# Schematics.net
KiCad netlist of a schematic drawn in EAGLE
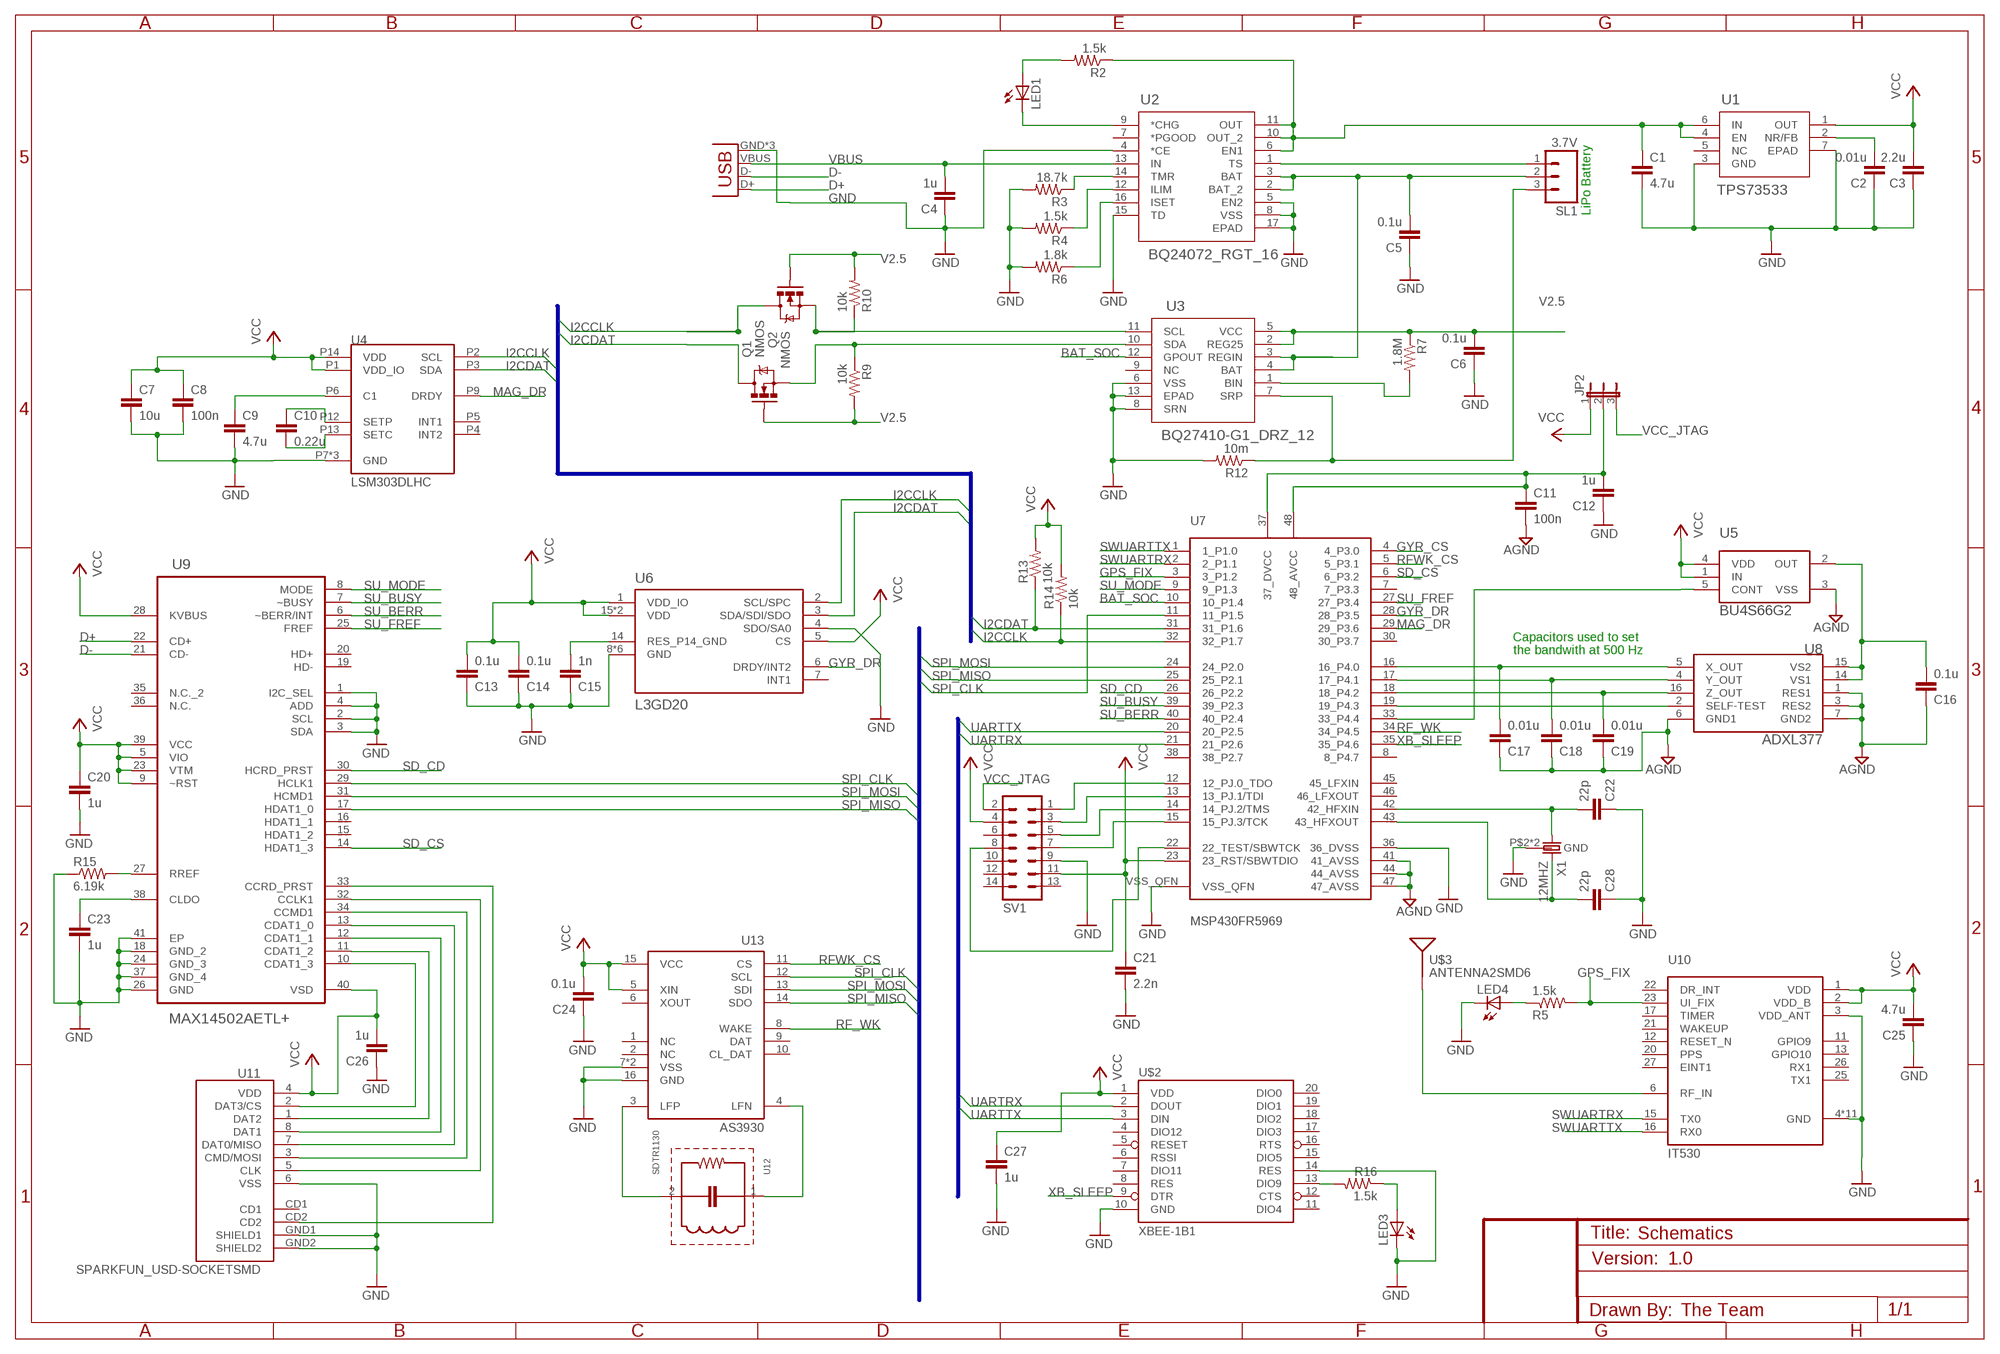
[diagram p0: schematic, sheet 1]

(export (version "E")
  (design (tool "Eeschema 10.0.6"))
  (components
    (comp (ref "C1")
      (value "4.7u")
      (footprint "eagle-import:C0603")
      (libsource (lib "eagle-import") (part "C-EUC0603"))
    )
    (comp (ref "C2")
      (value "0.01u")
      (footprint "eagle-import:C0603")
      (libsource (lib "eagle-import") (part "C-EUC0603"))
    )
    (comp (ref "C3")
      (value "2.2u")
      (footprint "eagle-import:C0603")
      (libsource (lib "eagle-import") (part "C-EUC0603"))
    )
    (comp (ref "C4")
      (value "1u")
      (footprint "eagle-import:C0603")
      (libsource (lib "eagle-import") (part "C-EUC0603"))
    )
    (comp (ref "C5")
      (value "0.1u")
      (footprint "eagle-import:C0603")
      (libsource (lib "eagle-import") (part "C-EUC0603"))
    )
    (comp (ref "C6")
      (value "0.1u")
      (footprint "eagle-import:C0603")
      (libsource (lib "eagle-import") (part "C-EUC0603"))
    )
    (comp (ref "C7")
      (value "10u")
      (footprint "eagle-import:C0603")
      (libsource (lib "eagle-import") (part "C-EUC0603"))
    )
    (comp (ref "C8")
      (value "100n")
      (footprint "eagle-import:C0603")
      (libsource (lib "eagle-import") (part "C-EUC0603"))
    )
    (comp (ref "C9")
      (value "4.7u")
      (footprint "eagle-import:C0603")
      (libsource (lib "eagle-import") (part "C-EUC0603"))
    )
    (comp (ref "C10")
      (value "0.22u")
      (footprint "eagle-import:C0603")
      (libsource (lib "eagle-import") (part "C-EUC0603"))
    )
    (comp (ref "C11")
      (value "100n")
      (footprint "eagle-import:C0603")
      (libsource (lib "eagle-import") (part "C-EUC0603"))
    )
    (comp (ref "C12")
      (value "1u")
      (footprint "eagle-import:C0603")
      (libsource (lib "eagle-import") (part "C-EUC0603"))
    )
    (comp (ref "C13")
      (value "0.1u")
      (footprint "eagle-import:C0603")
      (libsource (lib "eagle-import") (part "C-EUC0603"))
    )
    (comp (ref "C14")
      (value "0.1u")
      (footprint "eagle-import:C0603")
      (libsource (lib "eagle-import") (part "C-EUC0603"))
    )
    (comp (ref "C15")
      (value "1n")
      (footprint "eagle-import:C0603")
      (libsource (lib "eagle-import") (part "C-EUC0603"))
    )
    (comp (ref "C16")
      (value "0.1u")
      (footprint "eagle-import:C0603")
      (libsource (lib "eagle-import") (part "C-EUC0603"))
    )
    (comp (ref "C17")
      (value "0.01u")
      (footprint "eagle-import:C0603")
      (libsource (lib "eagle-import") (part "C-EUC0603"))
    )
    (comp (ref "C18")
      (value "0.01u")
      (footprint "eagle-import:C0603")
      (libsource (lib "eagle-import") (part "C-EUC0603"))
    )
    (comp (ref "C19")
      (value "0.01u")
      (footprint "eagle-import:C0603")
      (libsource (lib "eagle-import") (part "C-EUC0603"))
    )
    (comp (ref "C20")
      (value "1u")
      (footprint "eagle-import:C0603")
      (libsource (lib "eagle-import") (part "C-EUC0603"))
    )
    (comp (ref "C21")
      (value "2.2n")
      (footprint "eagle-import:C0603")
      (libsource (lib "eagle-import") (part "C-EUC0603"))
    )
    (comp (ref "C22")
      (value "22p")
      (footprint "eagle-import:C0603")
      (libsource (lib "eagle-import") (part "C-EUC0603"))
    )
    (comp (ref "C23")
      (value "1u")
      (footprint "eagle-import:C0603")
      (libsource (lib "eagle-import") (part "C-EUC0603"))
    )
    (comp (ref "C24")
      (value "0.1u")
      (footprint "eagle-import:C0603")
      (libsource (lib "eagle-import") (part "C-EUC0603"))
    )
    (comp (ref "C25")
      (value "4.7u")
      (footprint "eagle-import:C0603")
      (libsource (lib "eagle-import") (part "C-EUC0603"))
    )
    (comp (ref "C26")
      (value "1u")
      (footprint "eagle-import:C0603")
      (libsource (lib "eagle-import") (part "C-EUC0603"))
    )
    (comp (ref "C27")
      (value "1u")
      (footprint "eagle-import:C0603")
      (libsource (lib "eagle-import") (part "C-EUC0603"))
    )
    (comp (ref "C28")
      (value "22p")
      (footprint "eagle-import:C0603")
      (libsource (lib "eagle-import") (part "C-EUC0603"))
    )
    (comp (ref "JP1")
      (value "USB-MICROB")
      (footprint "eagle-import:USB-MICROB")
      (libsource (lib "eagle-import") (part "USB-MICROB"))
    )
    (comp (ref "JP2")
      (value "JP2E")
      (footprint "eagle-import:JP2")
      (libsource (lib "eagle-import") (part "JP2E"))
    )
    (comp (ref "LED1")
      (value "LED")
      (footprint "eagle-import:SMARTLED-TTW")
      (libsource (lib "eagle-import") (part "LED"))
    )
    (comp (ref "LED3")
      (value "LED")
      (footprint "eagle-import:SMARTLED-TTW")
      (libsource (lib "eagle-import") (part "LED"))
    )
    (comp (ref "LED4")
      (value "LED")
      (footprint "eagle-import:SMARTLED-TTW")
      (libsource (lib "eagle-import") (part "LED"))
    )
    (comp (ref "Q1")
      (value "NMOS")
      (footprint "eagle-import:SOT23")
      (libsource (lib "eagle-import") (part "MOSFET-NCHANNELBSS138"))
    )
    (comp (ref "Q2")
      (value "NMOS")
      (footprint "eagle-import:SOT23")
      (libsource (lib "eagle-import") (part "MOSFET-NCHANNELBSS138"))
    )
    (comp (ref "R2")
      (value "1.5k")
      (footprint "eagle-import:R0603")
      (libsource (lib "eagle-import") (part "R-US_R0603"))
    )
    (comp (ref "R3")
      (value "18.7k")
      (footprint "eagle-import:R0603")
      (libsource (lib "eagle-import") (part "R-US_R0603"))
    )
    (comp (ref "R4")
      (value "1.5k")
      (footprint "eagle-import:R0603")
      (libsource (lib "eagle-import") (part "R-US_R0603"))
    )
    (comp (ref "R5")
      (value "1.5k")
      (footprint "eagle-import:R0603")
      (libsource (lib "eagle-import") (part "R-US_R0603"))
    )
    (comp (ref "R6")
      (value "1.8k")
      (footprint "eagle-import:R0603")
      (libsource (lib "eagle-import") (part "R-US_R0603"))
    )
    (comp (ref "R7")
      (value "1.8M")
      (footprint "eagle-import:R0603")
      (libsource (lib "eagle-import") (part "R-US_R0603"))
    )
    (comp (ref "R9")
      (value "10k")
      (footprint "eagle-import:R0603")
      (libsource (lib "eagle-import") (part "R-US_R0603"))
    )
    (comp (ref "R10")
      (value "10k")
      (footprint "eagle-import:R0603")
      (libsource (lib "eagle-import") (part "R-US_R0603"))
    )
    (comp (ref "R12")
      (value "10m")
      (footprint "eagle-import:R0603")
      (libsource (lib "eagle-import") (part "R-US_R0603"))
    )
    (comp (ref "R13")
      (value "10k")
      (footprint "eagle-import:R0603")
      (libsource (lib "eagle-import") (part "R-US_R0603"))
    )
    (comp (ref "R14")
      (value "10k")
      (footprint "eagle-import:R0603")
      (libsource (lib "eagle-import") (part "R-US_R0603"))
    )
    (comp (ref "R15")
      (value "6.19k")
      (footprint "eagle-import:R0603")
      (libsource (lib "eagle-import") (part "R-US_R0603"))
    )
    (comp (ref "R16")
      (value "1.5k")
      (footprint "eagle-import:R0603")
      (libsource (lib "eagle-import") (part "R-US_R0603"))
    )
    (comp (ref "SL1")
      (value "3.7V")
      (footprint "eagle-import:03P")
      (libsource (lib "eagle-import") (part "M03"))
    )
    (comp (ref "SV1")
      (value "ML14L")
      (footprint "eagle-import:ML14L")
      (libsource (lib "eagle-import") (part "ML14L"))
    )
    (comp (ref "U$2")
      (value "XBEE-1B1")
      (footprint "eagle-import:XBEE-1")
      (libsource (lib "eagle-import") (part "XBEE-1B1"))
    )
    (comp (ref "U$3")
      (value "ANTENNA2SMD6")
      (footprint "eagle-import:ANTENNA-CHIP6")
      (libsource (lib "eagle-import") (part "ANTENNA2SMD6"))
    )
    (comp (ref "U1")
      (value "TPS73533")
      (footprint "eagle-import:DRV6_1P6X1")
      (fields
        (field (name "MANUFACTURER") "Texas Instruments")
        (field (name "MANUFACTURER_PART_NUMBER") "tps73533_drv_6")
      )
      (libsource (lib "eagle-import") (part "TPS73533_DRV_6"))
    )
    (comp (ref "U2")
      (value "BQ24072_RGT_16")
      (footprint "eagle-import:RGT16_1P7X1P7")
      (fields
        (field (name "GENERIC_PART_NUMBER") "BQ24072")
        (field (name "MANUFACTURER") "Texas Instruments")
      )
      (libsource (lib "eagle-import") (part "BQ24072_RGT_16"))
    )
    (comp (ref "U3")
      (value "BQ27410-G1_DRZ_12")
      (footprint "eagle-import:DRZ12_1P95X2P45")
      (fields
        (field (name "GENERIC_PART_NUMBER") "BQ27410-G1")
        (field (name "MANUFACTURER") "Texas Instruments")
      )
      (libsource (lib "eagle-import") (part "BQ27410-G1_DRZ_12"))
    )
    (comp (ref "U4")
      (value "LSM303DLHC")
      (footprint "eagle-import:LGA_3X5X1_14L")
      (libsource (lib "eagle-import") (part "LSM303DLHC"))
    )
    (comp (ref "U5")
      (value "BU4S66G2")
      (footprint "eagle-import:SSOP5")
      (libsource (lib "eagle-import") (part "BU4S66G2"))
    )
    (comp (ref "U6")
      (value "L3GD20")
      (footprint "eagle-import:L3GD20")
      (libsource (lib "eagle-import") (part "L3GD20"))
    )
    (comp (ref "U7")
      (value "MSP430FR5969")
      (footprint "eagle-import:RGZ(S-PQFP-N48)")
      (libsource (lib "eagle-import") (part "MSP430FR5969"))
    )
    (comp (ref "U8")
      (value "ADXL377")
      (footprint "eagle-import:LFCSP-16")
      (libsource (lib "eagle-import") (part "ADXL377"))
    )
    (comp (ref "U9")
      (value "MAX14502AETL+")
      (footprint "eagle-import:QFN40P500X500X80-41N")
      (libsource (lib "eagle-import") (part "MAX14502AETL+"))
    )
    (comp (ref "U10")
      (value "IT530")
      (footprint "eagle-import:IT530")
      (libsource (lib "eagle-import") (part "IT530"))
    )
    (comp (ref "U11")
      (value "SPARKFUN_USD-SOCKETSMD")
      (footprint "eagle-import:SPARKFUN_MICRO-SD-SOCKET-PP")
      (libsource (lib "eagle-import") (part "SPARKFUN_USD-SOCKETSMD"))
    )
    (comp (ref "U12")
      (value "SDTR1130")
      (footprint "eagle-import:SDTR1130-SMD")
      (libsource (lib "eagle-import") (part "SDTR1130"))
    )
    (comp (ref "U13")
      (value "AS3930")
      (footprint "eagle-import:AS3930")
      (libsource (lib "eagle-import") (part "AS3930"))
    )
    (comp (ref "X1")
      (value "12MHZ")
      (footprint "eagle-import:12MHZ")
      (libsource (lib "eagle-import") (part "12MHZ"))
    )
  )
  (nets
    (net (code "1") (name "/BAT_SOC") (class "Default")
      (node (ref "U3") (pin "12") (pinfunction "GPOUT_12") (pintype "output"))
      (node (ref "U7") (pin "10") (pinfunction "10_P1.4_10") (pintype "bidirectional"))
    )
    (net (code "2") (name "/D+") (class "Default")
      (node (ref "JP1") (pin "D+") (pinfunction "D+_D+") (pintype "bidirectional"))
      (node (ref "U9") (pin "22") (pinfunction "CD+_22") (pintype "passive"))
    )
    (net (code "3") (name "/D-") (class "Default")
      (node (ref "JP1") (pin "D-") (pinfunction "D-_D-") (pintype "bidirectional"))
      (node (ref "U9") (pin "21") (pinfunction "CD-_21") (pintype "passive"))
    )
    (net (code "4") (name "/GPS_FIX") (class "Default")
      (node (ref "R5") (pin "2") (pinfunction "2_2") (pintype "passive"))
      (node (ref "U10") (pin "23") (pinfunction "UI_FIX_23") (pintype "bidirectional"))
      (node (ref "U7") (pin "3") (pinfunction "3_P1.2_3") (pintype "bidirectional"))
    )
    (net (code "5") (name "/GYR_CS") (class "Default")
      (node (ref "U7") (pin "4") (pinfunction "4_P3.0_4") (pintype "bidirectional"))
    )
    (net (code "6") (name "/GYR_DR") (class "Default")
      (node (ref "U6") (pin "6") (pinfunction "DRDY/INT2_6") (pintype "output"))
      (node (ref "U7") (pin "28") (pinfunction "28_P3.5_28") (pintype "bidirectional"))
    )
    (net (code "7") (name "/I2CCLK") (class "Default")
      (node (ref "Q2") (pin "3") (pinfunction "D_3") (pintype "passive"))
      (node (ref "R14") (pin "1") (pinfunction "1_1") (pintype "passive"))
      (node (ref "U4") (pin "P2") (pinfunction "SCL_P2") (pintype "bidirectional"))
      (node (ref "U6") (pin "2") (pinfunction "SCL/SPC_2") (pintype "input"))
      (node (ref "U7") (pin "32") (pinfunction "32_P1.7_32") (pintype "bidirectional"))
    )
    (net (code "8") (name "/I2CDAT") (class "Default")
      (node (ref "Q1") (pin "3") (pinfunction "D_3") (pintype "passive"))
      (node (ref "R13") (pin "1") (pinfunction "1_1") (pintype "passive"))
      (node (ref "U4") (pin "P3") (pinfunction "SDA_P3") (pintype "bidirectional"))
      (node (ref "U6") (pin "3") (pinfunction "SDA/SDI/SDO_3") (pintype "bidirectional"))
      (node (ref "U7") (pin "31") (pinfunction "31_P1.6_31") (pintype "bidirectional"))
    )
    (net (code "9") (name "/MAG_DR") (class "Default")
      (node (ref "U4") (pin "P9") (pinfunction "DRDY_P9") (pintype "bidirectional"))
      (node (ref "U7") (pin "29") (pinfunction "29_P3.6_29") (pintype "bidirectional"))
    )
    (net (code "10") (name "/RFWK_CS") (class "Default")
      (node (ref "U13") (pin "11") (pinfunction "CS_11") (pintype "bidirectional"))
      (node (ref "U7") (pin "5") (pinfunction "5_P3.1_5") (pintype "bidirectional"))
    )
    (net (code "11") (name "/RF_WK") (class "Default")
      (node (ref "U13") (pin "8") (pinfunction "WAKE_8") (pintype "bidirectional"))
      (node (ref "U7") (pin "34") (pinfunction "34_P4.5_34") (pintype "bidirectional"))
    )
    (net (code "12") (name "/SD_CD") (class "Default")
      (node (ref "U7") (pin "26") (pinfunction "26_P2.2_26") (pintype "bidirectional"))
      (node (ref "U9") (pin "30") (pinfunction "HCRD_PRST_30") (pintype "passive"))
    )
    (net (code "13") (name "/SD_CS") (class "Default")
      (node (ref "U7") (pin "6") (pinfunction "6_P3.2_6") (pintype "bidirectional"))
      (node (ref "U9") (pin "14") (pinfunction "HDAT1_3_14") (pintype "passive"))
    )
    (net (code "14") (name "/SPI_CLK") (class "Default")
      (node (ref "U13") (pin "12") (pinfunction "SCL_12") (pintype "bidirectional"))
      (node (ref "U7") (pin "11") (pinfunction "11_P1.5_11") (pintype "bidirectional"))
      (node (ref "U9") (pin "29") (pinfunction "HCLK1_29") (pintype "input"))
    )
    (net (code "15") (name "/SPI_MISO") (class "Default")
      (node (ref "U13") (pin "14") (pinfunction "SDO_14") (pintype "bidirectional"))
      (node (ref "U7") (pin "25") (pinfunction "25_P2.1_25") (pintype "bidirectional"))
      (node (ref "U9") (pin "17") (pinfunction "HDAT1_0_17") (pintype "passive"))
    )
    (net (code "16") (name "/SPI_MOSI") (class "Default")
      (node (ref "U13") (pin "13") (pinfunction "SDI_13") (pintype "bidirectional"))
      (node (ref "U7") (pin "24") (pinfunction "24_P2.0_24") (pintype "bidirectional"))
      (node (ref "U9") (pin "31") (pinfunction "HCMD1_31") (pintype "passive"))
    )
    (net (code "17") (name "/SU_BERR") (class "Default")
      (node (ref "U7") (pin "40") (pinfunction "40_P2.4_40") (pintype "bidirectional"))
      (node (ref "U9") (pin "6") (pinfunction "~{BERR/INT}_6") (pintype "bidirectional"))
    )
    (net (code "18") (name "/SU_BUSY") (class "Default")
      (node (ref "U7") (pin "39") (pinfunction "39_P2.3_39") (pintype "bidirectional"))
      (node (ref "U9") (pin "7") (pinfunction "~{BUSY}_7") (pintype "output"))
    )
    (net (code "19") (name "/SU_FREF") (class "Default")
      (node (ref "U7") (pin "27") (pinfunction "27_P3.4_27") (pintype "bidirectional"))
      (node (ref "U9") (pin "25") (pinfunction "FREF_25") (pintype "passive"))
    )
    (net (code "20") (name "/SU_MODE") (class "Default")
      (node (ref "U7") (pin "9") (pinfunction "9_P1.3_9") (pintype "bidirectional"))
      (node (ref "U9") (pin "8") (pinfunction "MODE_8") (pintype "input"))
    )
    (net (code "21") (name "/SWUARTRX") (class "Default")
      (node (ref "U10") (pin "15") (pinfunction "TX0_15") (pintype "bidirectional"))
      (node (ref "U7") (pin "2") (pinfunction "2_P1.1_2") (pintype "bidirectional"))
    )
    (net (code "22") (name "/SWUARTTX") (class "Default")
      (node (ref "U10") (pin "16") (pinfunction "RX0_16") (pintype "bidirectional"))
      (node (ref "U7") (pin "1") (pinfunction "1_P1.0_1") (pintype "bidirectional"))
    )
    (net (code "23") (name "/UARTRX") (class "Default")
      (node (ref "U$2") (pin "2") (pinfunction "DOUT_2") (pintype "output"))
      (node (ref "U7") (pin "21") (pinfunction "21_P2.6_21") (pintype "bidirectional"))
    )
    (net (code "24") (name "/UARTTX") (class "Default")
      (node (ref "U$2") (pin "3") (pinfunction "DIN_3") (pintype "input"))
      (node (ref "U7") (pin "20") (pinfunction "20_P2.5_20") (pintype "bidirectional"))
    )
    (net (code "25") (name "/V2.5") (class "Default")
      (node (ref "C6") (pin "2") (pinfunction "2_2") (pintype "passive"))
      (node (ref "Q1") (pin "1") (pinfunction "G_1") (pintype "passive"))
      (node (ref "Q2") (pin "1") (pinfunction "G_1") (pintype "passive"))
      (node (ref "R10") (pin "2") (pinfunction "2_2") (pintype "passive"))
      (node (ref "R7") (pin "1") (pinfunction "1_1") (pintype "passive"))
      (node (ref "R9") (pin "2") (pinfunction "2_2") (pintype "passive"))
      (node (ref "U3") (pin "2") (pinfunction "REG25_2") (pintype "power_in"))
      (node (ref "U3") (pin "5") (pinfunction "VCC_5") (pintype "power_in"))
    )
    (net (code "26") (name "/VBUS") (class "Default")
      (node (ref "C4") (pin "2") (pinfunction "2_2") (pintype "passive"))
      (node (ref "JP1") (pin "VBUS") (pinfunction "VBUS_VBUS") (pintype "bidirectional"))
      (node (ref "U2") (pin "13") (pinfunction "IN_13") (pintype "input"))
    )
    (net (code "27") (name "/VCC_JTAG") (class "Default")
      (node (ref "JP2") (pin "3") (pinfunction "3_3") (pintype "passive"))
      (node (ref "SV1") (pin "2") (pinfunction "2_2") (pintype "passive"))
    )
    (net (code "28") (name "/XB_SLEEP") (class "Default")
      (node (ref "U$2") (pin "9") (pinfunction "DTR_9") (pintype "bidirectional"))
      (node (ref "U7") (pin "35") (pinfunction "35_P4.6_35") (pintype "bidirectional"))
    )
    (net (code "29") (name "AGND") (class "Default")
      (node (ref "C11") (pin "2") (pinfunction "2_2") (pintype "passive"))
      (node (ref "C16") (pin "1") (pinfunction "1_1") (pintype "passive"))
      (node (ref "C17") (pin "1") (pinfunction "1_1") (pintype "passive"))
      (node (ref "C18") (pin "1") (pinfunction "1_1") (pintype "passive"))
      (node (ref "C19") (pin "1") (pinfunction "1_1") (pintype "passive"))
      (node (ref "U5") (pin "3") (pinfunction "VSS_3") (pintype "bidirectional"))
      (node (ref "U7") (pin "41") (pinfunction "41_AVSS_41") (pintype "bidirectional"))
      (node (ref "U7") (pin "44") (pinfunction "44_AVSS_44") (pintype "bidirectional"))
      (node (ref "U7") (pin "47") (pinfunction "47_AVSS_47") (pintype "bidirectional"))
      (node (ref "U8") (pin "1") (pinfunction "RES1_1") (pintype "bidirectional"))
      (node (ref "U8") (pin "3") (pinfunction "RES2_3") (pintype "bidirectional"))
      (node (ref "U8") (pin "6") (pinfunction "GND1_6") (pintype "bidirectional"))
      (node (ref "U8") (pin "7") (pinfunction "GND2_7") (pintype "bidirectional"))
    )
    (net (code "30") (name "GND") (class "Default")
      (node (ref "C1") (pin "2") (pinfunction "2_2") (pintype "passive"))
      (node (ref "C12") (pin "1") (pinfunction "1_1") (pintype "passive"))
      (node (ref "C13") (pin "1") (pinfunction "1_1") (pintype "passive"))
      (node (ref "C14") (pin "1") (pinfunction "1_1") (pintype "passive"))
      (node (ref "C15") (pin "1") (pinfunction "1_1") (pintype "passive"))
      (node (ref "C2") (pin "1") (pinfunction "1_1") (pintype "passive"))
      (node (ref "C20") (pin "2") (pinfunction "2_2") (pintype "passive"))
      (node (ref "C21") (pin "2") (pinfunction "2_2") (pintype "passive"))
      (node (ref "C22") (pin "1") (pinfunction "1_1") (pintype "passive"))
      (node (ref "C23") (pin "2") (pinfunction "2_2") (pintype "passive"))
      (node (ref "C24") (pin "1") (pinfunction "1_1") (pintype "passive"))
      (node (ref "C25") (pin "1") (pinfunction "1_1") (pintype "passive"))
      (node (ref "C26") (pin "1") (pinfunction "1_1") (pintype "passive"))
      (node (ref "C27") (pin "2") (pinfunction "2_2") (pintype "passive"))
      (node (ref "C28") (pin "1") (pinfunction "1_1") (pintype "passive"))
      (node (ref "C3") (pin "1") (pinfunction "1_1") (pintype "passive"))
      (node (ref "C4") (pin "1") (pinfunction "1_1") (pintype "passive"))
      (node (ref "C5") (pin "1") (pinfunction "1_1") (pintype "passive"))
      (node (ref "C6") (pin "1") (pinfunction "1_1") (pintype "passive"))
      (node (ref "C7") (pin "2") (pinfunction "2_2") (pintype "passive"))
      (node (ref "C8") (pin "2") (pinfunction "2_2") (pintype "passive"))
      (node (ref "C9") (pin "2") (pinfunction "2_2") (pintype "passive"))
      (node (ref "JP1") (pin "GND") (pinfunction "GND_GND") (pintype "bidirectional"))
      (node (ref "JP1") (pin "MT1") (pinfunction "GND_MT1") (pintype "bidirectional"))
      (node (ref "JP1") (pin "MT2") (pinfunction "GND_MT2") (pintype "bidirectional"))
      (node (ref "LED3") (pin "C@1") (pinfunction "C_C@1") (pintype "passive"))
      (node (ref "LED4") (pin "C@1") (pinfunction "C_C@1") (pintype "passive"))
      (node (ref "R12") (pin "2") (pinfunction "2_2") (pintype "passive"))
      (node (ref "R15") (pin "1") (pinfunction "1_1") (pintype "passive"))
      (node (ref "R3") (pin "2") (pinfunction "2_2") (pintype "passive"))
      (node (ref "R4") (pin "2") (pinfunction "2_2") (pintype "passive"))
      (node (ref "R6") (pin "2") (pinfunction "2_2") (pintype "passive"))
      (node (ref "SV1") (pin "9") (pinfunction "9_9") (pintype "passive"))
      (node (ref "U$2") (pin "10") (pinfunction "GND_10") (pintype "power_in"))
      (node (ref "U$2") (pin "14") (pinfunction "RES_14") (pintype "bidirectional"))
      (node (ref "U1") (pin "3") (pinfunction "GND_3") (pintype "power_in"))
      (node (ref "U1") (pin "7") (pinfunction "EPAD_7") (pintype "passive"))
      (node (ref "U10") (pin "10") (pinfunction "GND_10") (pintype "bidirectional"))
      (node (ref "U10") (pin "14") (pinfunction "GND_14") (pintype "bidirectional"))
      (node (ref "U10") (pin "18") (pinfunction "GND_18") (pintype "bidirectional"))
      (node (ref "U10") (pin "19") (pinfunction "GND_19") (pintype "bidirectional"))
      (node (ref "U10") (pin "24") (pinfunction "GND_24") (pintype "bidirectional"))
      (node (ref "U10") (pin "28") (pinfunction "GND_28") (pintype "bidirectional"))
      (node (ref "U10") (pin "3") (pinfunction "VDD_ANT_3") (pintype "bidirectional"))
      (node (ref "U10") (pin "4") (pinfunction "GND_4") (pintype "bidirectional"))
      (node (ref "U10") (pin "5") (pinfunction "GND_5") (pintype "bidirectional"))
      (node (ref "U10") (pin "7") (pinfunction "GND_7") (pintype "bidirectional"))
      (node (ref "U10") (pin "8") (pinfunction "GND_8") (pintype "bidirectional"))
      (node (ref "U10") (pin "9") (pinfunction "GND_9") (pintype "bidirectional"))
      (node (ref "U11") (pin "6") (pinfunction "VSS_6") (pintype "bidirectional"))
      (node (ref "U11") (pin "GND1") (pinfunction "SHIELD1_GND1") (pintype "bidirectional"))
      (node (ref "U11") (pin "GND2") (pinfunction "SHIELD2_GND2") (pintype "bidirectional"))
      (node (ref "U13") (pin "16") (pinfunction "GND_16") (pintype "bidirectional"))
      (node (ref "U13") (pin "7") (pinfunction "VSS_7") (pintype "bidirectional"))
      (node (ref "U13") (pin "EXP") (pinfunction "VSS_EXP") (pintype "bidirectional"))
      (node (ref "U2") (pin "15") (pinfunction "TD_15") (pintype "input"))
      (node (ref "U2") (pin "17") (pinfunction "EPAD_17") (pintype "power_in"))
      (node (ref "U2") (pin "4") (pinfunction "*CE_4") (pintype "input"))
      (node (ref "U2") (pin "5") (pinfunction "EN2_5") (pintype "input"))
      (node (ref "U2") (pin "8") (pinfunction "VSS_8") (pintype "power_in"))
      (node (ref "U3") (pin "13") (pinfunction "EPAD_13") (pintype "power_in"))
      (node (ref "U3") (pin "6") (pinfunction "VSS_6") (pintype "power_in"))
      (node (ref "U3") (pin "8") (pinfunction "SRN_8") (pintype "input"))
      (node (ref "U4") (pin "P10") (pinfunction "GND_P10") (pintype "bidirectional"))
      (node (ref "U4") (pin "P11") (pinfunction "GND_P11") (pintype "bidirectional"))
      (node (ref "U4") (pin "P7") (pinfunction "GND_P7") (pintype "bidirectional"))
      (node (ref "U6") (pin "10") (pinfunction "GND_10") (pintype "bidirectional"))
      (node (ref "U6") (pin "11") (pinfunction "GND_11") (pintype "bidirectional"))
      (node (ref "U6") (pin "12") (pinfunction "GND_12") (pintype "bidirectional"))
      (node (ref "U6") (pin "13") (pinfunction "GND_13") (pintype "bidirectional"))
      (node (ref "U6") (pin "4") (pinfunction "SDO/SA0_4") (pintype "bidirectional"))
      (node (ref "U6") (pin "8") (pinfunction "GND_8") (pintype "bidirectional"))
      (node (ref "U6") (pin "9") (pinfunction "GND_9") (pintype "bidirectional"))
      (node (ref "U7") (pin "36") (pinfunction "36_DVSS_36") (pintype "bidirectional"))
      (node (ref "U7") (pin "VSS_QFN") (pinfunction "VSS_QFN_VSS_QFN") (pintype "bidirectional"))
      (node (ref "U9") (pin "1") (pinfunction "I2C_SEL_1") (pintype "input"))
      (node (ref "U9") (pin "18") (pinfunction "GND_2_18") (pintype "passive"))
      (node (ref "U9") (pin "2") (pinfunction "SCL_2") (pintype "input"))
      (node (ref "U9") (pin "24") (pinfunction "GND_3_24") (pintype "passive"))
      (node (ref "U9") (pin "26") (pinfunction "GND_26") (pintype "passive"))
      (node (ref "U9") (pin "3") (pinfunction "SDA_3") (pintype "bidirectional"))
      (node (ref "U9") (pin "37") (pinfunction "GND_4_37") (pintype "passive"))
      (node (ref "U9") (pin "4") (pinfunction "ADD_4") (pintype "input"))
      (node (ref "U9") (pin "41") (pinfunction "EP_41") (pintype "passive"))
      (node (ref "X1") (pin "P$2") (pinfunction "GND_P$2") (pintype "bidirectional"))
      (node (ref "X1") (pin "P$4") (pinfunction "GND_P$4") (pintype "bidirectional"))
    )
    (net (code "31") (name "Net-(LED1-A)") (class "Default")
      (node (ref "LED1") (pin "A@1") (pinfunction "A_A@1") (pintype "passive"))
      (node (ref "R2") (pin "2") (pinfunction "2_2") (pintype "passive"))
    )
    (net (code "32") (name "Net-(LED1-C)") (class "Default")
      (node (ref "LED1") (pin "C@1") (pinfunction "C_C@1") (pintype "passive"))
      (node (ref "U2") (pin "9") (pinfunction "*CHG_9") (pintype "output"))
    )
    (net (code "33") (name "Net-(LED3-A)") (class "Default")
      (node (ref "LED3") (pin "A@1") (pinfunction "A_A@1") (pintype "passive"))
      (node (ref "R16") (pin "1") (pinfunction "1_1") (pintype "passive"))
    )
    (net (code "34") (name "Net-(LED4-A)") (class "Default")
      (node (ref "LED4") (pin "A@1") (pinfunction "A_A@1") (pintype "passive"))
      (node (ref "R5") (pin "1") (pinfunction "1_1") (pintype "passive"))
    )
    (net (code "35") (name "Net-(Q1-S)") (class "Default")
      (node (ref "Q1") (pin "2") (pinfunction "S_2") (pintype "passive"))
      (node (ref "R9") (pin "1") (pinfunction "1_1") (pintype "passive"))
      (node (ref "U3") (pin "10") (pinfunction "SDA_10") (pintype "bidirectional"))
    )
    (net (code "36") (name "Net-(Q2-S)") (class "Default")
      (node (ref "Q2") (pin "2") (pinfunction "S_2") (pintype "passive"))
      (node (ref "R10") (pin "1") (pinfunction "1_1") (pintype "passive"))
      (node (ref "U3") (pin "11") (pinfunction "SCL_11") (pintype "input"))
    )
    (net (code "37") (name "Net-(U$2-DIO9)") (class "Default")
      (node (ref "R16") (pin "2") (pinfunction "2_2") (pintype "passive"))
      (node (ref "U$2") (pin "13") (pinfunction "DIO9_13") (pintype "bidirectional"))
    )
    (net (code "38") (name "Net-(U$3-SIGNAL)") (class "Default")
      (node (ref "U$3") (pin "1") (pinfunction "SIGNAL_1") (pintype "bidirectional"))
      (node (ref "U10") (pin "6") (pinfunction "RF_IN_6") (pintype "bidirectional"))
    )
    (net (code "39") (name "Net-(U1-EN)") (class "Default")
      (node (ref "C1") (pin "1") (pinfunction "1_1") (pintype "passive"))
      (node (ref "R2") (pin "1") (pinfunction "1_1") (pintype "passive"))
      (node (ref "U1") (pin "4") (pinfunction "EN_4") (pintype "passive"))
      (node (ref "U1") (pin "6") (pinfunction "IN_6") (pintype "input"))
      (node (ref "U2") (pin "10") (pinfunction "OUT_2_10") (pintype "output"))
      (node (ref "U2") (pin "11") (pinfunction "OUT_11") (pintype "output"))
      (node (ref "U2") (pin "6") (pinfunction "EN1_6") (pintype "input"))
    )
    (net (code "40") (name "Net-(U1-NR{slash}FB)") (class "Default")
      (node (ref "C2") (pin "2") (pinfunction "2_2") (pintype "passive"))
      (node (ref "U1") (pin "2") (pinfunction "NR/FB_2") (pintype "bidirectional"))
    )
    (net (code "41") (name "Net-(U2-BAT)") (class "Default")
      (node (ref "C5") (pin "2") (pinfunction "2_2") (pintype "passive"))
      (node (ref "SL1") (pin "2") (pinfunction "2_2") (pintype "passive"))
      (node (ref "U2") (pin "2") (pinfunction "BAT_2_2") (pintype "bidirectional"))
      (node (ref "U2") (pin "3") (pinfunction "BAT_3") (pintype "bidirectional"))
      (node (ref "U3") (pin "3") (pinfunction "REGIN_3") (pintype "power_in"))
      (node (ref "U3") (pin "4") (pinfunction "BAT_4") (pintype "input"))
    )
    (net (code "42") (name "Net-(U2-ILIM)") (class "Default")
      (node (ref "R4") (pin "1") (pinfunction "1_1") (pintype "passive"))
      (node (ref "U2") (pin "12") (pinfunction "ILIM_12") (pintype "input"))
    )
    (net (code "43") (name "Net-(U2-ISET)") (class "Default")
      (node (ref "R6") (pin "1") (pinfunction "1_1") (pintype "passive"))
      (node (ref "U2") (pin "16") (pinfunction "ISET_16") (pintype "bidirectional"))
    )
    (net (code "44") (name "Net-(U2-TMR)") (class "Default")
      (node (ref "R3") (pin "1") (pinfunction "1_1") (pintype "passive"))
      (node (ref "U2") (pin "14") (pinfunction "TMR_14") (pintype "input"))
    )
    (net (code "45") (name "Net-(U2-TS)") (class "Default")
      (node (ref "SL1") (pin "1") (pinfunction "1_1") (pintype "passive"))
      (node (ref "U2") (pin "1") (pinfunction "TS_1") (pintype "input"))
    )
    (net (code "46") (name "Net-(U3-BIN)") (class "Default")
      (node (ref "R7") (pin "2") (pinfunction "2_2") (pintype "passive"))
      (node (ref "U3") (pin "1") (pinfunction "BIN_1") (pintype "input"))
    )
    (net (code "47") (name "Net-(U3-SRP)") (class "Default")
      (node (ref "R12") (pin "1") (pinfunction "1_1") (pintype "passive"))
      (node (ref "SL1") (pin "3") (pinfunction "3_3") (pintype "passive"))
      (node (ref "U3") (pin "7") (pinfunction "SRP_7") (pintype "input"))
    )
    (net (code "48") (name "Net-(U4-C1)") (class "Default")
      (node (ref "C9") (pin "1") (pinfunction "1_1") (pintype "passive"))
      (node (ref "U4") (pin "P6") (pinfunction "C1_P6") (pintype "bidirectional"))
    )
    (net (code "49") (name "Net-(U4-SETC)") (class "Default")
      (node (ref "C10") (pin "2") (pinfunction "2_2") (pintype "passive"))
      (node (ref "U4") (pin "P13") (pinfunction "SETC_P13") (pintype "bidirectional"))
    )
    (net (code "50") (name "Net-(U4-SETP)") (class "Default")
      (node (ref "C10") (pin "1") (pinfunction "1_1") (pintype "passive"))
      (node (ref "U4") (pin "P12") (pinfunction "SETP_P12") (pintype "bidirectional"))
    )
    (net (code "51") (name "Net-(U5-CONT)") (class "Default")
      (node (ref "U5") (pin "5") (pinfunction "CONT_5") (pintype "bidirectional"))
      (node (ref "U7") (pin "33") (pinfunction "33_P4.4_33") (pintype "bidirectional"))
    )
    (net (code "52") (name "Net-(U5-OUT)") (class "Default")
      (node (ref "C16") (pin "2") (pinfunction "2_2") (pintype "passive"))
      (node (ref "U5") (pin "2") (pinfunction "OUT_2") (pintype "bidirectional"))
      (node (ref "U8") (pin "14") (pinfunction "VS1_14") (pintype "bidirectional"))
      (node (ref "U8") (pin "15") (pinfunction "VS2_15") (pintype "bidirectional"))
    )
    (net (code "53") (name "Net-(U6-RES_P14_GND)") (class "Default")
      (node (ref "C15") (pin "2") (pinfunction "2_2") (pintype "passive"))
      (node (ref "U6") (pin "14") (pinfunction "RES_P14_GND_14") (pintype "bidirectional"))
    )
    (net (code "54") (name "Net-(U7-12_PJ.0_TDO)") (class "Default")
      (node (ref "SV1") (pin "1") (pinfunction "1_1") (pintype "passive"))
      (node (ref "U7") (pin "12") (pinfunction "12_PJ.0_TDO_12") (pintype "bidirectional"))
    )
    (net (code "55") (name "Net-(U7-13_PJ.1{slash}TDI)") (class "Default")
      (node (ref "SV1") (pin "3") (pinfunction "3_3") (pintype "passive"))
      (node (ref "U7") (pin "13") (pinfunction "13_PJ.1/TDI_13") (pintype "bidirectional"))
    )
    (net (code "56") (name "Net-(U7-14_PJ.2{slash}TMS)") (class "Default")
      (node (ref "SV1") (pin "5") (pinfunction "5_5") (pintype "passive"))
      (node (ref "U7") (pin "14") (pinfunction "14_PJ.2/TMS_14") (pintype "bidirectional"))
    )
    (net (code "57") (name "Net-(U7-15_PJ.3{slash}TCK)") (class "Default")
      (node (ref "SV1") (pin "7") (pinfunction "7_7") (pintype "passive"))
      (node (ref "U7") (pin "15") (pinfunction "15_PJ.3/TCK_15") (pintype "bidirectional"))
    )
    (net (code "58") (name "Net-(U7-16_P4.0)") (class "Default")
      (node (ref "C17") (pin "2") (pinfunction "2_2") (pintype "passive"))
      (node (ref "U7") (pin "16") (pinfunction "16_P4.0_16") (pintype "bidirectional"))
      (node (ref "U8") (pin "5") (pinfunction "X_OUT_5") (pintype "bidirectional"))
    )
    (net (code "59") (name "Net-(U7-17_P4.1)") (class "Default")
      (node (ref "C18") (pin "2") (pinfunction "2_2") (pintype "passive"))
      (node (ref "U7") (pin "17") (pinfunction "17_P4.1_17") (pintype "bidirectional"))
      (node (ref "U8") (pin "4") (pinfunction "Y_OUT_4") (pintype "bidirectional"))
    )
    (net (code "60") (name "Net-(U7-18_P4.2)") (class "Default")
      (node (ref "C19") (pin "2") (pinfunction "2_2") (pintype "passive"))
      (node (ref "U7") (pin "18") (pinfunction "18_P4.2_18") (pintype "bidirectional"))
      (node (ref "U8") (pin "16") (pinfunction "Z_OUT_16") (pintype "bidirectional"))
    )
    (net (code "61") (name "Net-(U7-19_P4.3)") (class "Default")
      (node (ref "U7") (pin "19") (pinfunction "19_P4.3_19") (pintype "bidirectional"))
      (node (ref "U8") (pin "2") (pinfunction "SELF-TEST_2") (pintype "bidirectional"))
    )
    (net (code "62") (name "Net-(U7-22_TEST{slash}SBWTCK)") (class "Default")
      (node (ref "SV1") (pin "8") (pinfunction "8_8") (pintype "passive"))
      (node (ref "U7") (pin "22") (pinfunction "22_TEST/SBWTCK_22") (pintype "bidirectional"))
    )
    (net (code "63") (name "Net-(U7-37_DVCC)") (class "Default")
      (node (ref "C11") (pin "1") (pinfunction "1_1") (pintype "passive"))
      (node (ref "C12") (pin "2") (pinfunction "2_2") (pintype "passive"))
      (node (ref "JP2") (pin "2") (pinfunction "2_2") (pintype "passive"))
      (node (ref "U7") (pin "37") (pinfunction "37_DVCC_37") (pintype "bidirectional"))
      (node (ref "U7") (pin "48") (pinfunction "48_AVCC_48") (pintype "bidirectional"))
    )
    (net (code "64") (name "Net-(U7-42_HFXIN)") (class "Default")
      (node (ref "C22") (pin "2") (pinfunction "2_2") (pintype "passive"))
      (node (ref "U7") (pin "42") (pinfunction "42_HFXIN_42") (pintype "bidirectional"))
      (node (ref "X1") (pin "P$1") (pinfunction "1_P$1") (pintype "passive"))
    )
    (net (code "65") (name "Net-(U7-43_HFXOUT)") (class "Default")
      (node (ref "C28") (pin "2") (pinfunction "2_2") (pintype "passive"))
      (node (ref "U7") (pin "43") (pinfunction "43_HFXOUT_43") (pintype "bidirectional"))
      (node (ref "X1") (pin "P$3") (pinfunction "2_P$3") (pintype "passive"))
    )
    (net (code "66") (name "Net-(U9-CCRD_PRST)") (class "Default")
      (node (ref "U11") (pin "CD2") (pinfunction "CD2_CD2") (pintype "bidirectional"))
      (node (ref "U9") (pin "33") (pinfunction "CCRD_PRST_33") (pintype "passive"))
    )
    (net (code "67") (name "Net-(U9-CLDO)") (class "Default")
      (node (ref "C23") (pin "1") (pinfunction "1_1") (pintype "passive"))
      (node (ref "U9") (pin "38") (pinfunction "CLDO_38") (pintype "power_in"))
    )
    (net (code "68") (name "Net-(U9-RREF)") (class "Default")
      (node (ref "R15") (pin "2") (pinfunction "2_2") (pintype "passive"))
      (node (ref "U9") (pin "27") (pinfunction "RREF_27") (pintype "passive"))
    )
    (net (code "69") (name "Net-(U11-CLK)") (class "Default")
      (node (ref "U11") (pin "5") (pinfunction "CLK_5") (pintype "bidirectional"))
      (node (ref "U9") (pin "32") (pinfunction "CCLK1_32") (pintype "input"))
    )
    (net (code "70") (name "Net-(U11-CMD{slash}MOSI)") (class "Default")
      (node (ref "U11") (pin "3") (pinfunction "CMD/MOSI_3") (pintype "bidirectional"))
      (node (ref "U9") (pin "34") (pinfunction "CCMD1_34") (pintype "passive"))
    )
    (net (code "71") (name "Net-(U11-DAT0{slash}MISO)") (class "Default")
      (node (ref "U11") (pin "7") (pinfunction "DAT0/MISO_7") (pintype "bidirectional"))
      (node (ref "U9") (pin "13") (pinfunction "CDAT1_0_13") (pintype "passive"))
    )
    (net (code "72") (name "Net-(U11-DAT1)") (class "Default")
      (node (ref "U11") (pin "8") (pinfunction "DAT1_8") (pintype "bidirectional"))
      (node (ref "U9") (pin "12") (pinfunction "CDAT1_1_12") (pintype "passive"))
    )
    (net (code "73") (name "Net-(U11-DAT2)") (class "Default")
      (node (ref "U11") (pin "1") (pinfunction "DAT2_1") (pintype "bidirectional"))
      (node (ref "U9") (pin "11") (pinfunction "CDAT1_2_11") (pintype "passive"))
    )
    (net (code "74") (name "Net-(U11-DAT3{slash}CS)") (class "Default")
      (node (ref "U11") (pin "2") (pinfunction "DAT3/CS_2") (pintype "bidirectional"))
      (node (ref "U9") (pin "10") (pinfunction "CDAT1_3_10") (pintype "passive"))
    )
    (net (code "75") (name "Net-(U13-LFN)") (class "Default")
      (node (ref "U12") (pin "1") (pinfunction "1_1") (pintype "bidirectional"))
      (node (ref "U13") (pin "4") (pinfunction "LFN_4") (pintype "bidirectional"))
    )
    (net (code "76") (name "Net-(U13-LFP)") (class "Default")
      (node (ref "U12") (pin "2") (pinfunction "2_2") (pintype "bidirectional"))
      (node (ref "U13") (pin "3") (pinfunction "LFP_3") (pintype "bidirectional"))
    )
    (net (code "77") (name "VCC") (class "Default")
      (node (ref "C13") (pin "2") (pinfunction "2_2") (pintype "passive"))
      (node (ref "C14") (pin "2") (pinfunction "2_2") (pintype "passive"))
      (node (ref "C20") (pin "1") (pinfunction "1_1") (pintype "passive"))
      (node (ref "C21") (pin "1") (pinfunction "1_1") (pintype "passive"))
      (node (ref "C24") (pin "2") (pinfunction "2_2") (pintype "passive"))
      (node (ref "C25") (pin "2") (pinfunction "2_2") (pintype "passive"))
      (node (ref "C26") (pin "2") (pinfunction "2_2") (pintype "passive"))
      (node (ref "C27") (pin "1") (pinfunction "1_1") (pintype "passive"))
      (node (ref "C3") (pin "2") (pinfunction "2_2") (pintype "passive"))
      (node (ref "C7") (pin "1") (pinfunction "1_1") (pintype "passive"))
      (node (ref "C8") (pin "1") (pinfunction "1_1") (pintype "passive"))
      (node (ref "JP2") (pin "1") (pinfunction "1_1") (pintype "passive"))
      (node (ref "R13") (pin "2") (pinfunction "2_2") (pintype "passive"))
      (node (ref "R14") (pin "2") (pinfunction "2_2") (pintype "passive"))
      (node (ref "SV1") (pin "11") (pinfunction "11_11") (pintype "passive"))
      (node (ref "SV1") (pin "4") (pinfunction "4_4") (pintype "passive"))
      (node (ref "U$2") (pin "1") (pinfunction "VDD_1") (pintype "power_in"))
      (node (ref "U1") (pin "1") (pinfunction "OUT_1") (pintype "power_in"))
      (node (ref "U10") (pin "1") (pinfunction "VDD_1") (pintype "bidirectional"))
      (node (ref "U10") (pin "2") (pinfunction "VDD_B_2") (pintype "bidirectional"))
      (node (ref "U11") (pin "4") (pinfunction "VDD_4") (pintype "bidirectional"))
      (node (ref "U13") (pin "15") (pinfunction "VCC_15") (pintype "bidirectional"))
      (node (ref "U13") (pin "5") (pinfunction "XIN_5") (pintype "bidirectional"))
      (node (ref "U4") (pin "P1") (pinfunction "VDD_IO_P1") (pintype "bidirectional"))
      (node (ref "U4") (pin "P14") (pinfunction "VDD_P14") (pintype "bidirectional"))
      (node (ref "U5") (pin "1") (pinfunction "IN_1") (pintype "bidirectional"))
      (node (ref "U5") (pin "4") (pinfunction "VDD_4") (pintype "bidirectional"))
      (node (ref "U6") (pin "1") (pinfunction "VDD_IO_1") (pintype "bidirectional"))
      (node (ref "U6") (pin "15") (pinfunction "VDD_15") (pintype "bidirectional"))
      (node (ref "U6") (pin "16") (pinfunction "VDD_16") (pintype "bidirectional"))
      (node (ref "U6") (pin "5") (pinfunction "CS_5") (pintype "input"))
      (node (ref "U7") (pin "23") (pinfunction "23_RST/SBWTDIO_23") (pintype "bidirectional"))
      (node (ref "U9") (pin "23") (pinfunction "VTM_23") (pintype "passive"))
      (node (ref "U9") (pin "28") (pinfunction "KVBUS_28") (pintype "passive"))
      (node (ref "U9") (pin "39") (pinfunction "VCC_39") (pintype "power_in"))
      (node (ref "U9") (pin "40") (pinfunction "VSD_40") (pintype "power_in"))
      (node (ref "U9") (pin "5") (pinfunction "VIO_5") (pintype "passive"))
      (node (ref "U9") (pin "9") (pinfunction "~{RST}_9") (pintype "input"))
    )
    (net (code "78") (name "unconnected-(SV1-Pad6)") (class "Default")
      (node (ref "SV1") (pin "6") (pinfunction "6_6") (pintype "passive"))
    )
    (net (code "79") (name "unconnected-(SV1-Pad10)") (class "Default")
      (node (ref "SV1") (pin "10") (pinfunction "10_10") (pintype "passive"))
    )
    (net (code "80") (name "unconnected-(SV1-Pad12)") (class "Default")
      (node (ref "SV1") (pin "12") (pinfunction "12_12") (pintype "passive"))
    )
    (net (code "81") (name "unconnected-(SV1-Pad13)") (class "Default")
      (node (ref "SV1") (pin "13") (pinfunction "13_13") (pintype "passive"))
    )
    (net (code "82") (name "unconnected-(SV1-Pad14)") (class "Default")
      (node (ref "SV1") (pin "14") (pinfunction "14_14") (pintype "passive"))
    )
    (net (code "83") (name "unconnected-(U$2-CTS-Pad12)") (class "Default")
      (node (ref "U$2") (pin "12") (pinfunction "CTS_12") (pintype "output"))
    )
    (net (code "84") (name "unconnected-(U$2-DIO0-Pad20)") (class "Default")
      (node (ref "U$2") (pin "20") (pinfunction "DIO0_20") (pintype "bidirectional"))
    )
    (net (code "85") (name "unconnected-(U$2-DIO1-Pad19)") (class "Default")
      (node (ref "U$2") (pin "19") (pinfunction "DIO1_19") (pintype "bidirectional"))
    )
    (net (code "86") (name "unconnected-(U$2-DIO2-Pad18)") (class "Default")
      (node (ref "U$2") (pin "18") (pinfunction "DIO2_18") (pintype "bidirectional"))
    )
    (net (code "87") (name "unconnected-(U$2-DIO3-Pad17)") (class "Default")
      (node (ref "U$2") (pin "17") (pinfunction "DIO3_17") (pintype "bidirectional"))
    )
    (net (code "88") (name "unconnected-(U$2-DIO4-Pad11)") (class "Default")
      (node (ref "U$2") (pin "11") (pinfunction "DIO4_11") (pintype "bidirectional"))
    )
    (net (code "89") (name "unconnected-(U$2-DIO5-Pad15)") (class "Default")
      (node (ref "U$2") (pin "15") (pinfunction "DIO5_15") (pintype "bidirectional"))
    )
    (net (code "90") (name "unconnected-(U$2-DIO11-Pad7)") (class "Default")
      (node (ref "U$2") (pin "7") (pinfunction "DIO11_7") (pintype "bidirectional"))
    )
    (net (code "91") (name "unconnected-(U$2-DIO12-Pad4)") (class "Default")
      (node (ref "U$2") (pin "4") (pinfunction "DIO12_4") (pintype "bidirectional"))
    )
    (net (code "92") (name "unconnected-(U$2-RES-Pad8)") (class "Default")
      (node (ref "U$2") (pin "8") (pinfunction "RES_8") (pintype "bidirectional"))
    )
    (net (code "93") (name "unconnected-(U$2-RESET-Pad5)") (class "Default")
      (node (ref "U$2") (pin "5") (pinfunction "RESET_5") (pintype "input"))
    )
    (net (code "94") (name "unconnected-(U$2-RSSI-Pad6)") (class "Default")
      (node (ref "U$2") (pin "6") (pinfunction "RSSI_6") (pintype "bidirectional"))
    )
    (net (code "95") (name "unconnected-(U$2-RTS-Pad16)") (class "Default")
      (node (ref "U$2") (pin "16") (pinfunction "RTS_16") (pintype "input"))
    )
    (net (code "96") (name "unconnected-(U1-NC-Pad5)") (class "Default")
      (node (ref "U1") (pin "5") (pinfunction "NC_5") (pintype "passive"))
    )
    (net (code "97") (name "unconnected-(U2-*PGOOD-Pad7)") (class "Default")
      (node (ref "U2") (pin "7") (pinfunction "*PGOOD_7") (pintype "output"))
    )
    (net (code "98") (name "unconnected-(U3-NC-Pad9)") (class "Default")
      (node (ref "U3") (pin "9") (pinfunction "NC_9") (pintype "no_connect"))
    )
    (net (code "99") (name "unconnected-(U4-INT1-PadP5)") (class "Default")
      (node (ref "U4") (pin "P5") (pinfunction "INT1_P5") (pintype "bidirectional"))
    )
    (net (code "100") (name "unconnected-(U4-INT2-PadP4)") (class "Default")
      (node (ref "U4") (pin "P4") (pinfunction "INT2_P4") (pintype "bidirectional"))
    )
    (net (code "101") (name "unconnected-(U6-INT1-Pad7)") (class "Default")
      (node (ref "U6") (pin "7") (pinfunction "INT1_7") (pintype "output"))
    )
    (net (code "102") (name "unconnected-(U7-7_P3.3-Pad7)") (class "Default")
      (node (ref "U7") (pin "7") (pinfunction "7_P3.3_7") (pintype "bidirectional"))
    )
    (net (code "103") (name "unconnected-(U7-8_P4.7-Pad8)") (class "Default")
      (node (ref "U7") (pin "8") (pinfunction "8_P4.7_8") (pintype "bidirectional"))
    )
    (net (code "104") (name "unconnected-(U7-30_P3.7-Pad30)") (class "Default")
      (node (ref "U7") (pin "30") (pinfunction "30_P3.7_30") (pintype "bidirectional"))
    )
    (net (code "105") (name "unconnected-(U7-38_P2.7-Pad38)") (class "Default")
      (node (ref "U7") (pin "38") (pinfunction "38_P2.7_38") (pintype "bidirectional"))
    )
    (net (code "106") (name "unconnected-(U7-45_LFXIN-Pad45)") (class "Default")
      (node (ref "U7") (pin "45") (pinfunction "45_LFXIN_45") (pintype "bidirectional"))
    )
    (net (code "107") (name "unconnected-(U7-46_LFXOUT-Pad46)") (class "Default")
      (node (ref "U7") (pin "46") (pinfunction "46_LFXOUT_46") (pintype "bidirectional"))
    )
    (net (code "108") (name "unconnected-(U9-HD+-Pad20)") (class "Default")
      (node (ref "U9") (pin "20") (pinfunction "HD+_20") (pintype "passive"))
    )
    (net (code "109") (name "unconnected-(U9-HD--Pad19)") (class "Default")
      (node (ref "U9") (pin "19") (pinfunction "HD-_19") (pintype "passive"))
    )
    (net (code "110") (name "unconnected-(U9-HDAT1_1-Pad16)") (class "Default")
      (node (ref "U9") (pin "16") (pinfunction "HDAT1_1_16") (pintype "passive"))
    )
    (net (code "111") (name "unconnected-(U9-HDAT1_2-Pad15)") (class "Default")
      (node (ref "U9") (pin "15") (pinfunction "HDAT1_2_15") (pintype "passive"))
    )
    (net (code "112") (name "unconnected-(U9-N.C.-Pad36)") (class "Default")
      (node (ref "U9") (pin "36") (pinfunction "N.C._36") (pintype "no_connect"))
    )
    (net (code "113") (name "unconnected-(U9-N.C._2-Pad35)") (class "Default")
      (node (ref "U9") (pin "35") (pinfunction "N.C._2_35") (pintype "no_connect"))
    )
    (net (code "114") (name "unconnected-(U10-DR_INT-Pad22)") (class "Default")
      (node (ref "U10") (pin "22") (pinfunction "DR_INT_22") (pintype "bidirectional"))
    )
    (net (code "115") (name "unconnected-(U10-EINT1-Pad27)") (class "Default")
      (node (ref "U10") (pin "27") (pinfunction "EINT1_27") (pintype "bidirectional"))
    )
    (net (code "116") (name "unconnected-(U10-GPIO9-Pad11)") (class "Default")
      (node (ref "U10") (pin "11") (pinfunction "GPIO9_11") (pintype "bidirectional"))
    )
    (net (code "117") (name "unconnected-(U10-GPIO10-Pad13)") (class "Default")
      (node (ref "U10") (pin "13") (pinfunction "GPIO10_13") (pintype "bidirectional"))
    )
    (net (code "118") (name "unconnected-(U10-PPS-Pad20)") (class "Default")
      (node (ref "U10") (pin "20") (pinfunction "PPS_20") (pintype "bidirectional"))
    )
    (net (code "119") (name "unconnected-(U10-RESET_N-Pad12)") (class "Default")
      (node (ref "U10") (pin "12") (pinfunction "RESET_N_12") (pintype "bidirectional"))
    )
    (net (code "120") (name "unconnected-(U10-RX1-Pad26)") (class "Default")
      (node (ref "U10") (pin "26") (pinfunction "RX1_26") (pintype "bidirectional"))
    )
    (net (code "121") (name "unconnected-(U10-TIMER-Pad17)") (class "Default")
      (node (ref "U10") (pin "17") (pinfunction "TIMER_17") (pintype "bidirectional"))
    )
    (net (code "122") (name "unconnected-(U10-TX1-Pad25)") (class "Default")
      (node (ref "U10") (pin "25") (pinfunction "TX1_25") (pintype "bidirectional"))
    )
    (net (code "123") (name "unconnected-(U10-WAKEUP-Pad21)") (class "Default")
      (node (ref "U10") (pin "21") (pinfunction "WAKEUP_21") (pintype "bidirectional"))
    )
    (net (code "124") (name "unconnected-(U11-PadCD1)") (class "Default")
      (node (ref "U11") (pin "CD1") (pinfunction "CD1_CD1") (pintype "bidirectional"))
    )
    (net (code "125") (name "unconnected-(U13-CL_DAT-Pad10)") (class "Default")
      (node (ref "U13") (pin "10") (pinfunction "CL_DAT_10") (pintype "bidirectional"))
    )
    (net (code "126") (name "unconnected-(U13-DAT-Pad9)") (class "Default")
      (node (ref "U13") (pin "9") (pinfunction "DAT_9") (pintype "bidirectional"))
    )
    (net (code "127") (name "unconnected-(U13-NC-Pad1)") (class "Default")
      (node (ref "U13") (pin "1") (pinfunction "NC_1") (pintype "bidirectional"))
    )
    (net (code "128") (name "unconnected-(U13-NC-Pad2)") (class "Default")
      (node (ref "U13") (pin "2") (pinfunction "NC_2") (pintype "bidirectional"))
    )
    (net (code "129") (name "unconnected-(U13-XOUT-Pad6)") (class "Default")
      (node (ref "U13") (pin "6") (pinfunction "XOUT_6") (pintype "bidirectional"))
    )
  )
)
